# PROC051D_SOP_Headers_Reference.net
KiCad netlist of a schematic drawn in Altium Designer
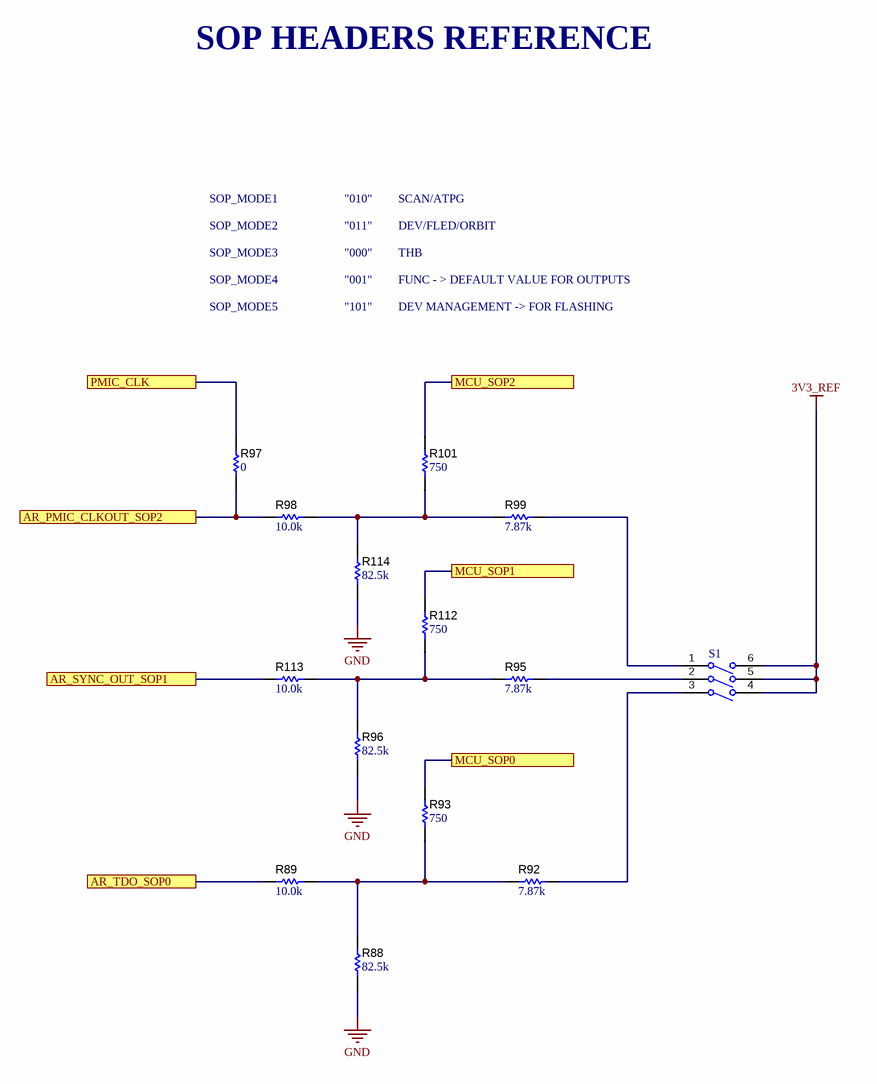
[diagram p0: PROC051D_SOP_Headers_Reference.SchDoc]

(export (version "E")
  (design (tool "Eeschema 10.0.6"))
  (components
    (comp (ref "R88")
      (value "CRCW040282K5FKED")
      (footprint "0402L")
      (description "RES, 82.5 k, 1%, 0.063 W, AEC-Q200 Grade 0, 0402")
      (fields (field (name "MANUFACTURER") "Vishay-Dale") (field (name "VALUEDISPLAYED") "82.5k"))
      (libsource (lib "Altium Vault - TI") (part "Resistor"))
    )
    (comp (ref "R89")
      (value "CRCW040210K0FKED")
      (footprint "0402L")
      (description "RES, 10.0 k, 1%, 0.063 W, AEC-Q200 Grade 0, 0402")
      (fields (field (name "MANUFACTURER") "Vishay-Dale") (field (name "VALUEDISPLAYED") "10.0k"))
      (libsource (lib "Altium Vault - TI") (part "Resistor"))
    )
    (comp (ref "R92")
      (value "CRCW04027K87FKED")
      (footprint "0402L")
      (description "RES, 7.87 k, 1%, 0.063 W, AEC-Q200 Grade 0, 0402")
      (fields (field (name "MANUFACTURER") "Vishay-Dale") (field (name "VALUEDISPLAYED") "7.87k"))
      (libsource (lib "Altium Vault - TI") (part "Resistor"))
    )
    (comp (ref "R93")
      (value "CRCW0402750RFKED")
      (footprint "0402L")
      (description "RES, 750, 1%, 0.063 W, AEC-Q200 Grade 0, 0402")
      (fields (field (name "MANUFACTURER") "Vishay-Dale") (field (name "VALUEDISPLAYED") "750"))
      (libsource (lib "Altium Vault - TI") (part "Resistor"))
    )
    (comp (ref "R95")
      (value "CRCW04027K87FKED")
      (footprint "0402L")
      (description "RES, 7.87 k, 1%, 0.063 W, AEC-Q200 Grade 0, 0402")
      (fields (field (name "MANUFACTURER") "Vishay-Dale") (field (name "VALUEDISPLAYED") "7.87k"))
      (libsource (lib "Altium Vault - TI") (part "Resistor"))
    )
    (comp (ref "R96")
      (value "CRCW040282K5FKED")
      (footprint "0402L")
      (description "RES, 82.5 k, 1%, 0.063 W, AEC-Q200 Grade 0, 0402")
      (fields (field (name "MANUFACTURER") "Vishay-Dale") (field (name "VALUEDISPLAYED") "82.5k"))
      (libsource (lib "Altium Vault - TI") (part "Resistor"))
    )
    (comp (ref "R97")
      (value "ERJ-2GE0R00X")
      (footprint "0402L")
      (description "RES, 0, 5%, 0.1 W, AEC-Q200 Grade 0, 0402")
      (fields (field (name "MANUFACTURER") "Panasonic") (field (name "VALUEDISPLAYED") "0"))
      (libsource (lib "Altium Vault - TI") (part "Resistor"))
    )
    (comp (ref "R98")
      (value "CRCW040210K0FKED")
      (footprint "0402L")
      (description "RES, 10.0 k, 1%, 0.063 W, AEC-Q200 Grade 0, 0402")
      (fields (field (name "MANUFACTURER") "Vishay-Dale") (field (name "VALUEDISPLAYED") "10.0k"))
      (libsource (lib "Altium Vault - TI") (part "Resistor"))
    )
    (comp (ref "R99")
      (value "CRCW04027K87FKED")
      (footprint "0402L")
      (description "RES, 7.87 k, 1%, 0.063 W, AEC-Q200 Grade 0, 0402")
      (fields (field (name "MANUFACTURER") "Vishay-Dale") (field (name "VALUEDISPLAYED") "7.87k"))
      (libsource (lib "Altium Vault - TI") (part "Resistor"))
    )
    (comp (ref "R101")
      (value "CRCW0402750RFKED")
      (footprint "0402L")
      (description "RES, 750, 1%, 0.063 W, AEC-Q200 Grade 0, 0402")
      (fields (field (name "MANUFACTURER") "Vishay-Dale") (field (name "VALUEDISPLAYED") "750"))
      (libsource (lib "Altium Vault - TI") (part "Resistor"))
    )
    (comp (ref "R112")
      (value "CRCW0402750RFKED")
      (footprint "0402L")
      (description "RES, 750, 1%, 0.063 W, AEC-Q200 Grade 0, 0402")
      (fields (field (name "MANUFACTURER") "Vishay-Dale") (field (name "VALUEDISPLAYED") "750"))
      (libsource (lib "Altium Vault - TI") (part "Resistor"))
    )
    (comp (ref "R113")
      (value "CRCW040210K0FKED")
      (footprint "0402L")
      (description "RES, 10.0 k, 1%, 0.063 W, AEC-Q200 Grade 0, 0402")
      (fields (field (name "MANUFACTURER") "Vishay-Dale") (field (name "VALUEDISPLAYED") "10.0k"))
      (libsource (lib "Altium Vault - TI") (part "Resistor"))
    )
    (comp (ref "R114")
      (value "CRCW040282K5FKED")
      (footprint "0402L")
      (description "RES, 82.5 k, 1%, 0.063 W, AEC-Q200 Grade 0, 0402")
      (fields (field (name "MANUFACTURER") "Vishay-Dale") (field (name "VALUEDISPLAYED") "82.5k"))
      (libsource (lib "Altium Vault - TI") (part "Resistor"))
    )
    (comp (ref "S1")
      (value "219-3MST")
      (footprint "SW_219-3MST")
      (description "Switch, SPST, Slide, Off-On, 3 Pos, 0.1A, 20V, SMD")
      (fields
        (field (name "MANUFACTURER") "CTS Electrocomponents")
        (field (name "PUBLISHER") "Texas Instruments")
      )
      (libsource (lib "Altium Vault - TI") (part "CMP-0002269-1"))
    )
  )
  (nets
    (net (code "1") (name "/AR_PMIC_CLKOUT_SOP2") (class "Default")
      (node (ref "R97") (pin "1") (pinfunction "1_1") (pintype "passive"))
      (node (ref "R98") (pin "1") (pinfunction "1_1") (pintype "passive"))
    )
    (net (code "2") (name "/AR_SYNC_OUT_SOP1") (class "Default")
      (node (ref "R113") (pin "1") (pinfunction "1_1") (pintype "passive"))
    )
    (net (code "3") (name "/AR_TDO_SOP0") (class "Default")
      (node (ref "R89") (pin "1") (pinfunction "1_1") (pintype "passive"))
    )
    (net (code "4") (name "/MCU_SOP0") (class "Default")
      (node (ref "R93") (pin "2") (pinfunction "2_2") (pintype "passive"))
    )
    (net (code "5") (name "/MCU_SOP1") (class "Default")
      (node (ref "R112") (pin "2") (pinfunction "2_2") (pintype "passive"))
    )
    (net (code "6") (name "/MCU_SOP2") (class "Default")
      (node (ref "R101") (pin "2") (pinfunction "2_2") (pintype "passive"))
    )
    (net (code "7") (name "/PMIC_CLK") (class "Default")
      (node (ref "R97") (pin "2") (pinfunction "2_2") (pintype "passive"))
    )
    (net (code "8") (name "3V3_REF") (class "Default")
      (node (ref "S1") (pin "4") (pinfunction "B3_4") (pintype "passive"))
      (node (ref "S1") (pin "5") (pinfunction "B2_5") (pintype "passive"))
      (node (ref "S1") (pin "6") (pinfunction "B1_6") (pintype "passive"))
    )
    (net (code "9") (name "GND") (class "Default")
      (node (ref "R114") (pin "1") (pinfunction "1_1") (pintype "passive"))
      (node (ref "R88") (pin "1") (pinfunction "1_1") (pintype "passive"))
      (node (ref "R96") (pin "1") (pinfunction "1_1") (pintype "passive"))
    )
    (net (code "10") (name "Net-(R88-Pad2)") (class "Default")
      (node (ref "R88") (pin "2") (pinfunction "2_2") (pintype "passive"))
      (node (ref "R89") (pin "2") (pinfunction "2_2") (pintype "passive"))
      (node (ref "R92") (pin "1") (pinfunction "1_1") (pintype "passive"))
      (node (ref "R93") (pin "1") (pinfunction "1_1") (pintype "passive"))
    )
    (net (code "11") (name "Net-(R101-Pad1)") (class "Default")
      (node (ref "R101") (pin "1") (pinfunction "1_1") (pintype "passive"))
      (node (ref "R114") (pin "2") (pinfunction "2_2") (pintype "passive"))
      (node (ref "R98") (pin "2") (pinfunction "2_2") (pintype "passive"))
      (node (ref "R99") (pin "1") (pinfunction "1_1") (pintype "passive"))
    )
    (net (code "12") (name "Net-(R112-Pad1)") (class "Default")
      (node (ref "R112") (pin "1") (pinfunction "1_1") (pintype "passive"))
      (node (ref "R113") (pin "2") (pinfunction "2_2") (pintype "passive"))
      (node (ref "R95") (pin "1") (pinfunction "1_1") (pintype "passive"))
      (node (ref "R96") (pin "2") (pinfunction "2_2") (pintype "passive"))
    )
    (net (code "13") (name "Net-(S1-A1)") (class "Default")
      (node (ref "R99") (pin "2") (pinfunction "2_2") (pintype "passive"))
      (node (ref "S1") (pin "1") (pinfunction "A1_1") (pintype "passive"))
    )
    (net (code "14") (name "Net-(S1-A2)") (class "Default")
      (node (ref "R95") (pin "2") (pinfunction "2_2") (pintype "passive"))
      (node (ref "S1") (pin "2") (pinfunction "A2_2") (pintype "passive"))
    )
    (net (code "15") (name "Net-(S1-A3)") (class "Default")
      (node (ref "R92") (pin "2") (pinfunction "2_2") (pintype "passive"))
      (node (ref "S1") (pin "3") (pinfunction "A3_3") (pintype "passive"))
    )
  )
)
